# Mainboard_Breakbeam_Interface.net
KiCad netlist of a schematic drawn in Altium Designer
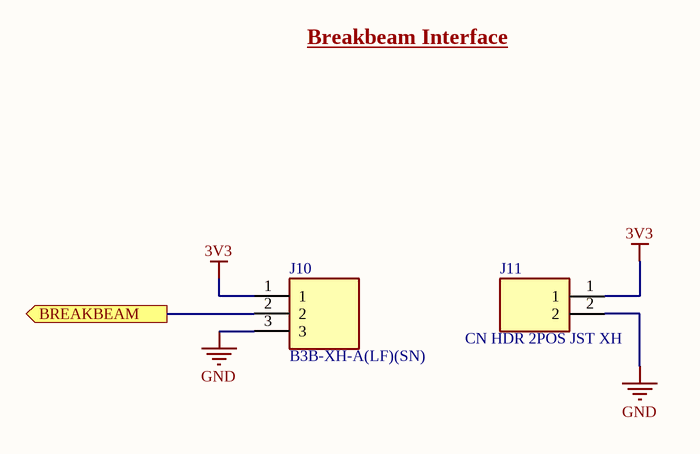
[diagram p0: Mainboard_Breakbeam_Interface.SchDoc]

(export (version "E")
  (design (tool "Eeschema 10.0.6"))
  (components
    (comp (ref "J10")
      (value "B3B-XH-A(LF)(SN)")
      (footprint "JST_B3B-XH-A(LF)(SN)")
      (description "CN 3POS TH JST XH")
      (fields (field (name "MF") "JST Sales"))
      (libsource (lib "AltiumLibraries") (part "CN 3POS TH JSTXH"))
    )
    (comp (ref "J11")
      (value "CN HDR 2POS JST XH")
      (footprint "JST_B2B-XH-A(LF)(SN)")
      (description "Connector Header Through Hole 2 position 0.098 _2.50mm_\r\nJST XH")
      (fields (field (name "MP") "B2B-XH-A_LF__SN_") (field (name "MF") "JST Sales"))
      (libsource (lib "AltiumLibraries") (part "CN HDR 2POS JST XH"))
    )
  )
  (nets
    (net (code "1") (name "/BREAKBEAM") (class "Default")
      (node (ref "J10") (pin "2") (pinfunction "2_2") (pintype "passive"))
    )
    (net (code "2") (name "3V3") (class "Default")
      (node (ref "J10") (pin "1") (pinfunction "1_1") (pintype "passive"))
      (node (ref "J11") (pin "1") (pinfunction "1_1") (pintype "passive"))
    )
    (net (code "3") (name "GND") (class "Default")
      (node (ref "J10") (pin "3") (pinfunction "3_3") (pintype "passive"))
      (node (ref "J11") (pin "2") (pinfunction "2_2") (pintype "passive"))
    )
  )
)
